# LoraWan_shield_v01.net
KiCad netlist of a schematic drawn in EAGLE
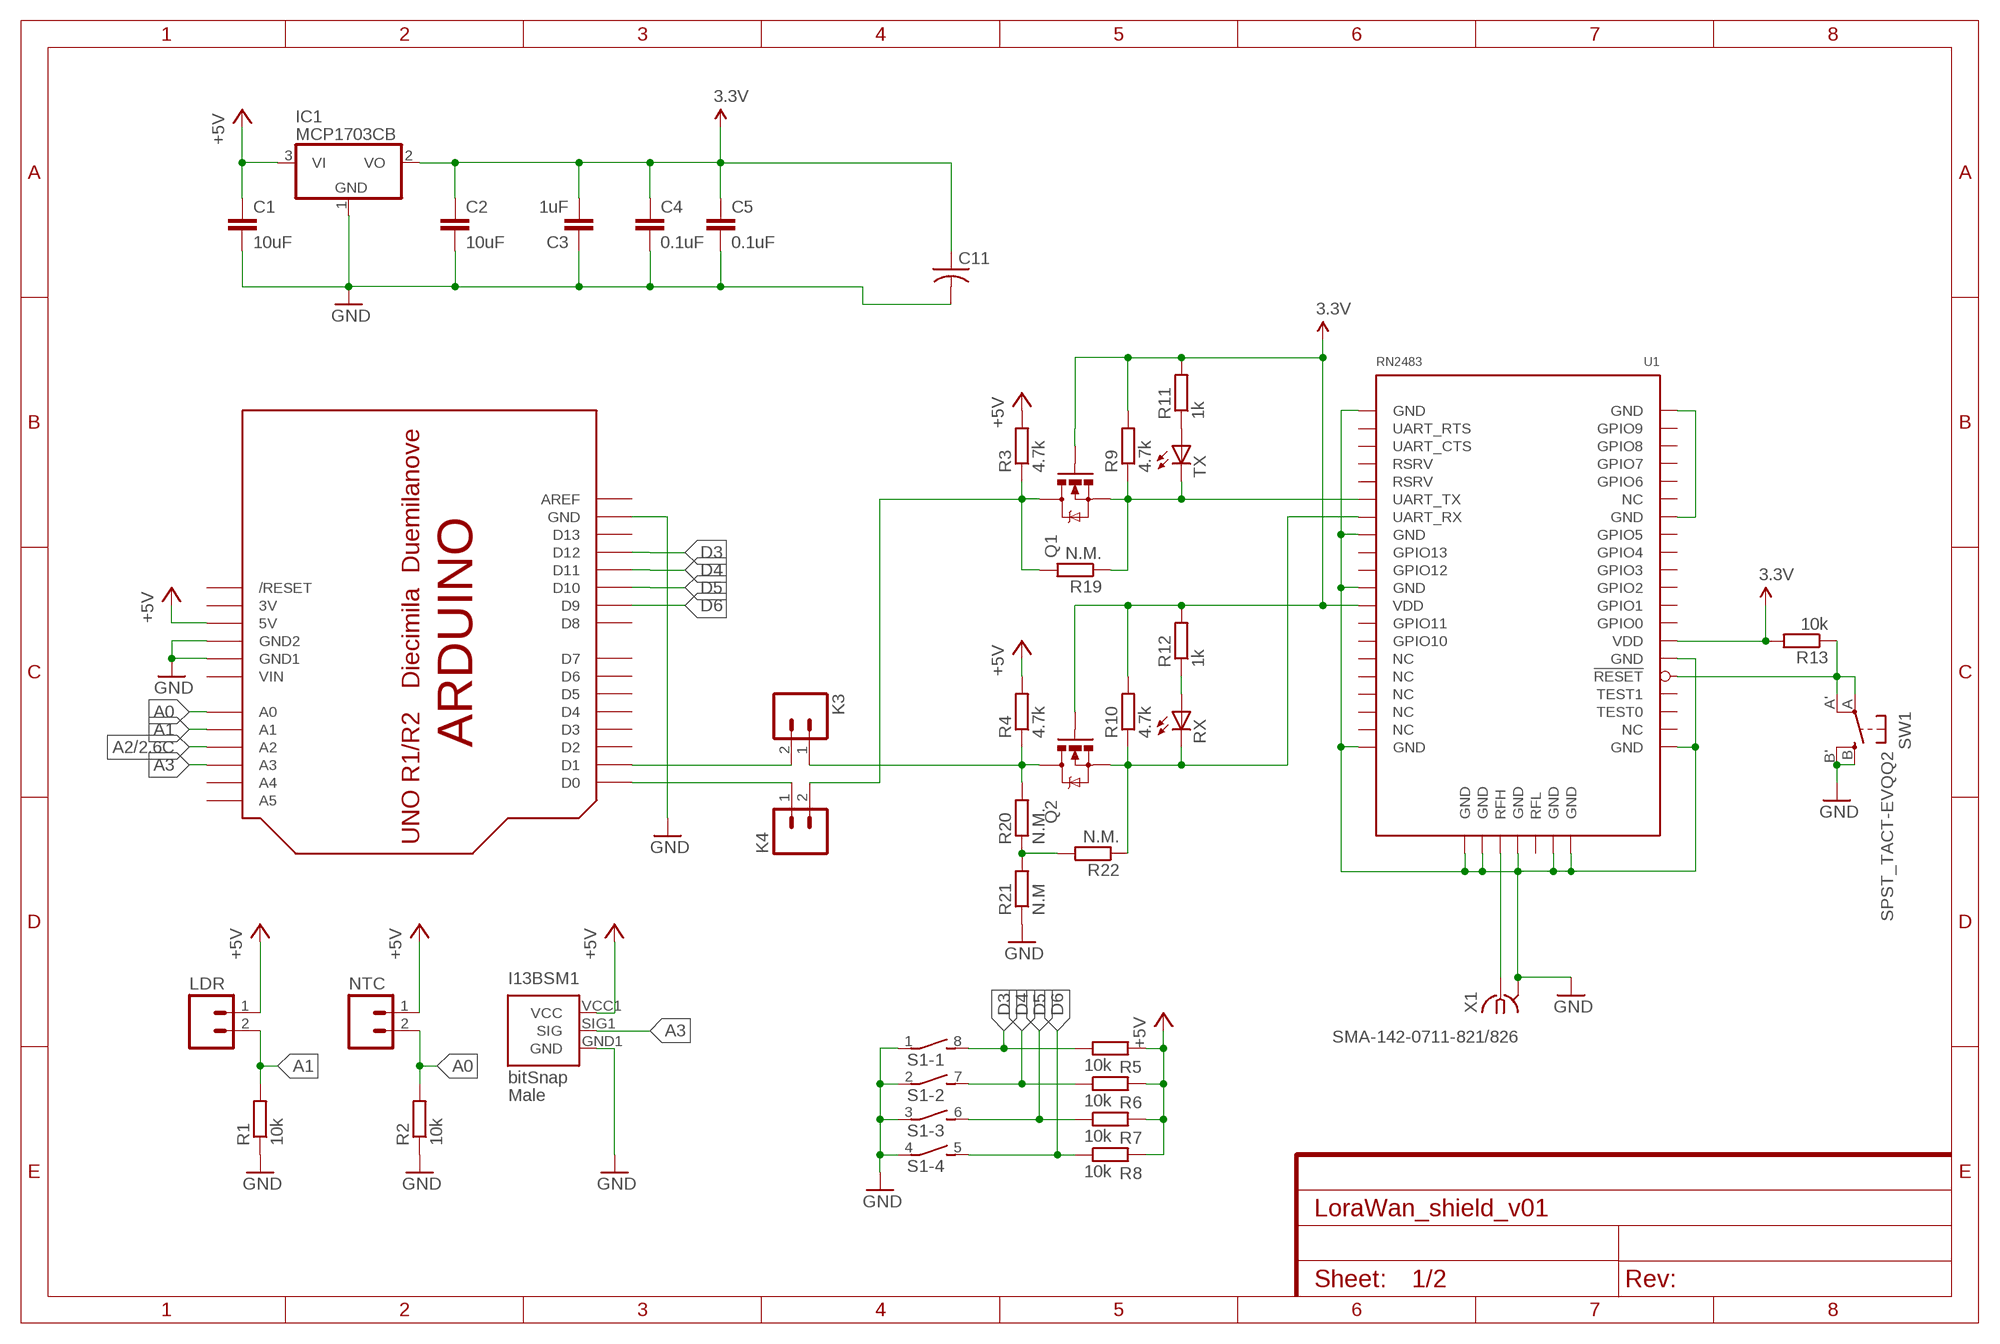
[diagram p0: schematic, sheet 1]
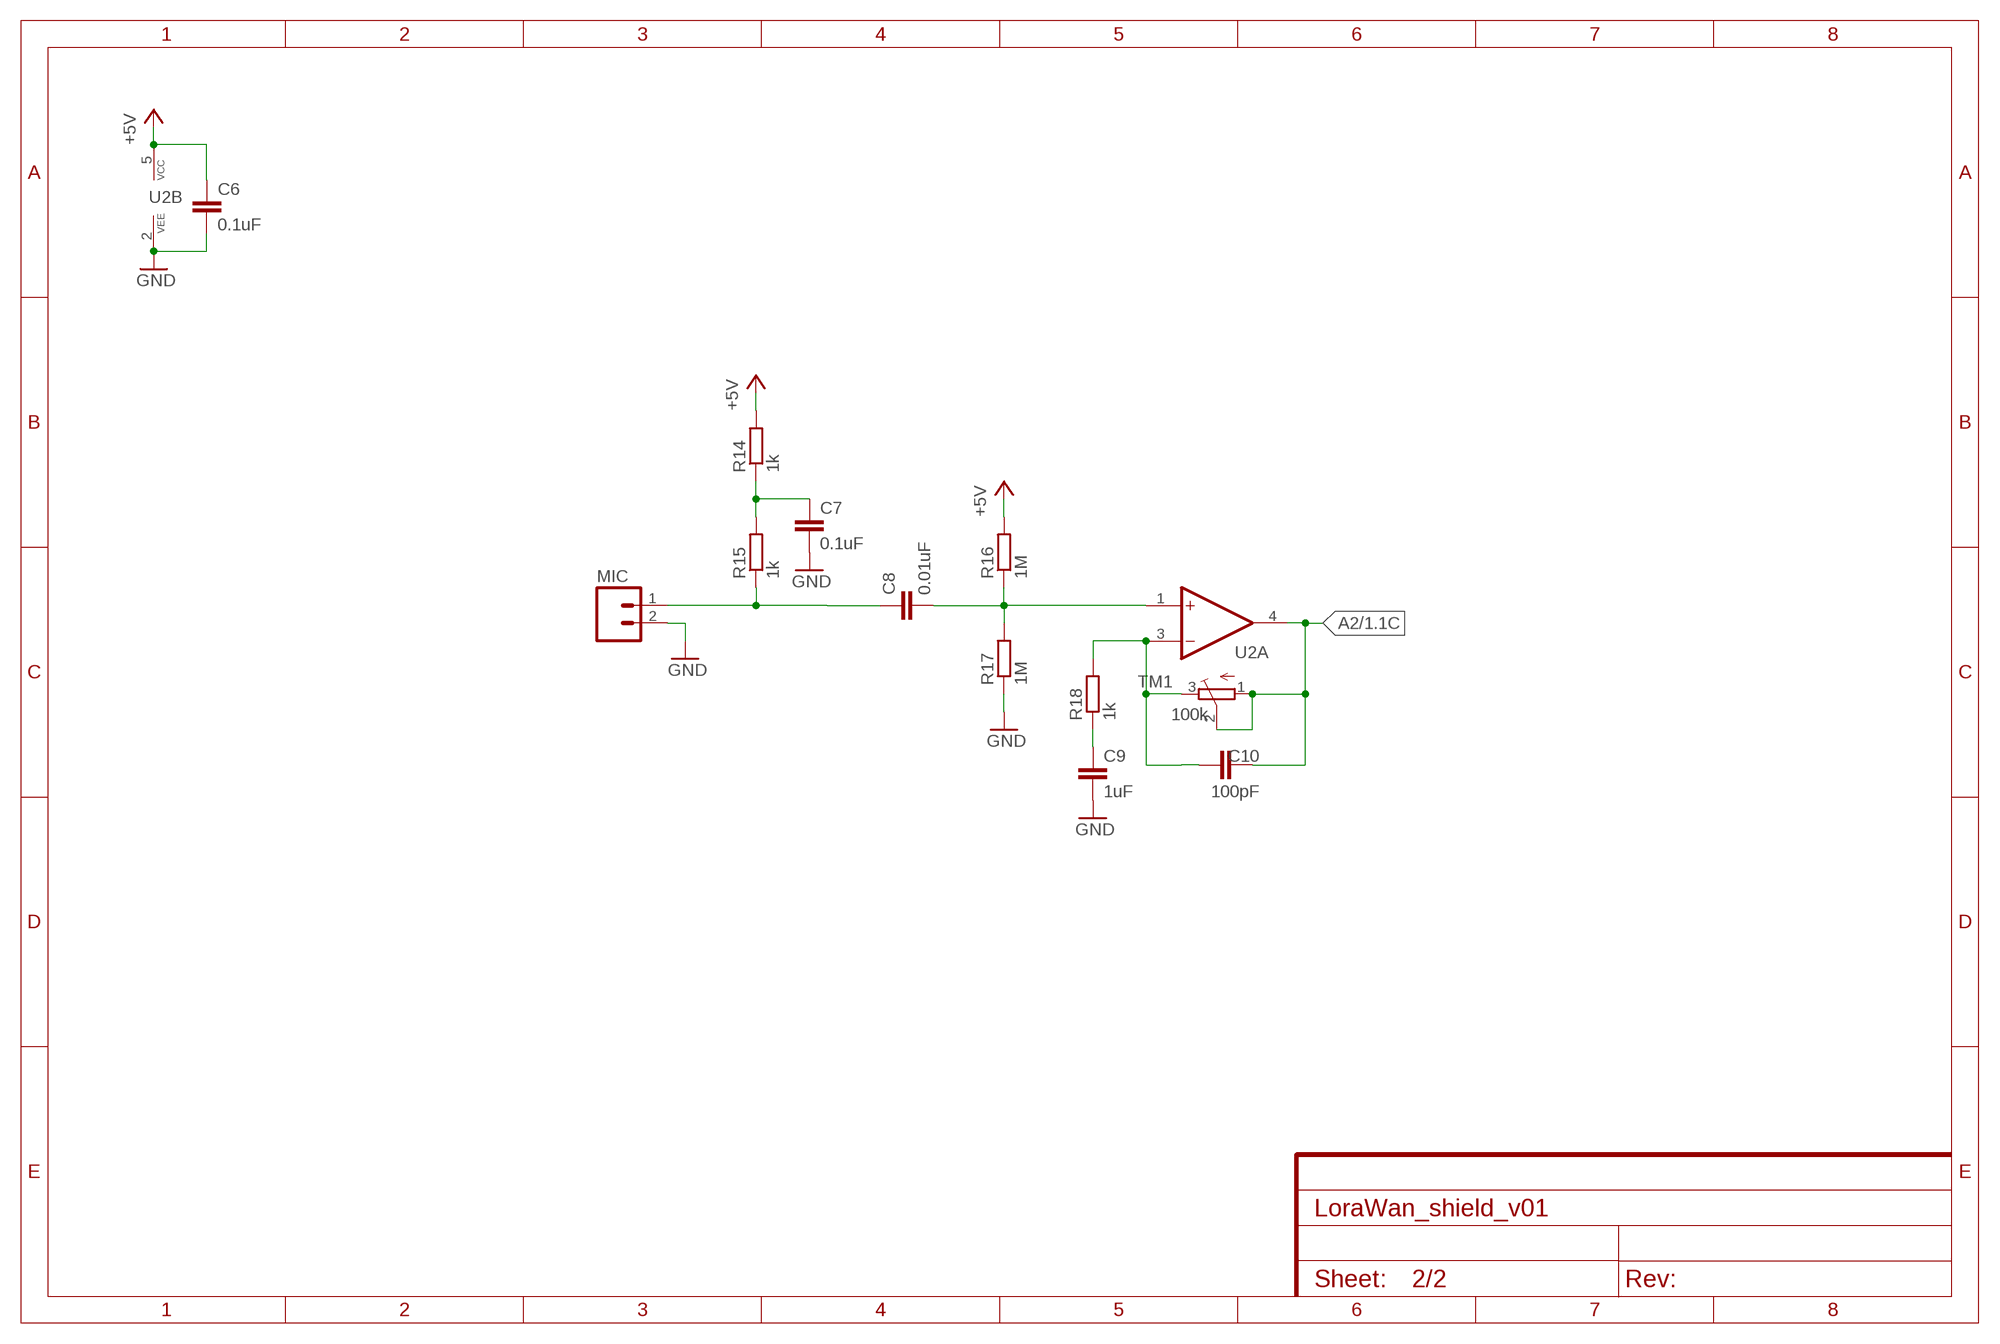
[diagram p1: schematic, sheet 2]

(export (version "E")
  (design (tool "Eeschema 10.0.6"))
  (components
    (comp (ref "C6")
      (value "0.1uF")
      (footprint "eagle-import:C0603K")
      (libsource (lib "eagle-import") (part "C-EUC0603K"))
    )
    (comp (ref "C7")
      (value "0.1uF")
      (footprint "eagle-import:C0603K")
      (libsource (lib "eagle-import") (part "C-EUC0603K"))
    )
    (comp (ref "C8")
      (value "0.01uF")
      (footprint "eagle-import:C0603K")
      (libsource (lib "eagle-import") (part "C-EUC0603K"))
    )
    (comp (ref "C9")
      (value "1uF")
      (footprint "eagle-import:C0603K")
      (libsource (lib "eagle-import") (part "C-EUC0603K"))
    )
    (comp (ref "C10")
      (value "100pF")
      (footprint "eagle-import:C0603K")
      (libsource (lib "eagle-import") (part "C-EUC0603K"))
    )
    (comp (ref "MIC")
      (value "M02LOCK_LONGPADS")
      (footprint "eagle-import:1X02_LOCK_LONGPADS")
      (libsource (lib "eagle-import") (part "M02LOCK_LONGPADS"))
    )
    (comp (ref "R14")
      (value "1k")
      (footprint "eagle-import:R0603")
      (libsource (lib "eagle-import") (part "R-EU_R0603"))
    )
    (comp (ref "R15")
      (value "1k")
      (footprint "eagle-import:R0603")
      (libsource (lib "eagle-import") (part "R-EU_R0603"))
    )
    (comp (ref "R16")
      (value "1M")
      (footprint "eagle-import:R0603")
      (libsource (lib "eagle-import") (part "R-EU_R0603"))
    )
    (comp (ref "R17")
      (value "1M")
      (footprint "eagle-import:R0603")
      (libsource (lib "eagle-import") (part "R-EU_R0603"))
    )
    (comp (ref "R18")
      (value "1k")
      (footprint "eagle-import:R0603")
      (libsource (lib "eagle-import") (part "R-EU_R0603"))
    )
    (comp (ref "TM1")
      (value "100k")
      (footprint "eagle-import:TC33X")
      (libsource (lib "eagle-import") (part "TRIMPOTTC33X"))
    )
    (comp (ref "U2")
      (value "MAX4466EXK+T")
      (footprint "eagle-import:SC70")
      (libsource (lib "eagle-import") (part "MAX4466EXK+T"))
    )
    (comp (ref "ARD1")
      (value "ARDUINO-NOHOLE")
      (footprint "eagle-import:ARDUINO-NOHOLE")
      (libsource (lib "eagle-import") (part "ARDUINO-NOHOLE"))
    )
    (comp (ref "C1")
      (value "10uF")
      (footprint "eagle-import:C0603K")
      (libsource (lib "eagle-import") (part "C-EUC0603K"))
    )
    (comp (ref "C2")
      (value "10uF")
      (footprint "eagle-import:C0603K")
      (libsource (lib "eagle-import") (part "C-EUC0603K"))
    )
    (comp (ref "C3")
      (value "1uF")
      (footprint "eagle-import:C0603K")
      (libsource (lib "eagle-import") (part "C-EUC0603K"))
    )
    (comp (ref "C4")
      (value "0.1uF")
      (footprint "eagle-import:C0603K")
      (libsource (lib "eagle-import") (part "C-EUC0603K"))
    )
    (comp (ref "C5")
      (value "0.1uF")
      (footprint "eagle-import:C0603K")
      (libsource (lib "eagle-import") (part "C-EUC0603K"))
    )
    (comp (ref "C11")
      (value "C-USC0603")
      (footprint "eagle-import:C0603")
      (libsource (lib "eagle-import") (part "C-USC0603"))
    )
    (comp (ref "I13BSM1")
      (value "BITSNAP_V03_MALE")
      (footprint "eagle-import:BITSNAP_V03_MALE")
      (libsource (lib "eagle-import") (part "BITSNAP_V03_MALE"))
    )
    (comp (ref "IC1")
      (value "MCP1703CB")
      (footprint "eagle-import:SOT23")
      (libsource (lib "eagle-import") (part "MCP1703CB"))
    )
    (comp (ref "K3")
      (value "M02LOCK_LONGPADS")
      (footprint "eagle-import:1X02_LOCK_LONGPADS")
      (libsource (lib "eagle-import") (part "M02LOCK_LONGPADS"))
    )
    (comp (ref "K4")
      (value "M02LOCK_LONGPADS")
      (footprint "eagle-import:1X02_LOCK_LONGPADS")
      (libsource (lib "eagle-import") (part "M02LOCK_LONGPADS"))
    )
    (comp (ref "LDR")
      (value "M02LOCK_LONGPADS")
      (footprint "eagle-import:1X02_LOCK_LONGPADS")
      (libsource (lib "eagle-import") (part "M02LOCK_LONGPADS"))
    )
    (comp (ref "NTC")
      (value "M02LOCK_LONGPADS")
      (footprint "eagle-import:1X02_LOCK_LONGPADS")
      (libsource (lib "eagle-import") (part "M02LOCK_LONGPADS"))
    )
    (comp (ref "Q1")
      (value "DMG1012T")
      (footprint "eagle-import:SOT523")
      (libsource (lib "eagle-import") (part "DMG1012T"))
    )
    (comp (ref "Q2")
      (value "DMG1012T")
      (footprint "eagle-import:SOT523")
      (libsource (lib "eagle-import") (part "DMG1012T"))
    )
    (comp (ref "R1")
      (value "10k")
      (footprint "eagle-import:R0603")
      (libsource (lib "eagle-import") (part "R-EU_R0603"))
    )
    (comp (ref "R2")
      (value "10k")
      (footprint "eagle-import:R0603")
      (libsource (lib "eagle-import") (part "R-EU_R0603"))
    )
    (comp (ref "R3")
      (value "4.7k")
      (footprint "eagle-import:R0603")
      (libsource (lib "eagle-import") (part "R-EU_R0603"))
    )
    (comp (ref "R4")
      (value "4.7k")
      (footprint "eagle-import:R0603")
      (libsource (lib "eagle-import") (part "R-EU_R0603"))
    )
    (comp (ref "R5")
      (value "10k")
      (footprint "eagle-import:R0603")
      (libsource (lib "eagle-import") (part "R-EU_R0603"))
    )
    (comp (ref "R6")
      (value "10k")
      (footprint "eagle-import:R0603")
      (libsource (lib "eagle-import") (part "R-EU_R0603"))
    )
    (comp (ref "R7")
      (value "10k")
      (footprint "eagle-import:R0603")
      (libsource (lib "eagle-import") (part "R-EU_R0603"))
    )
    (comp (ref "R8")
      (value "10k")
      (footprint "eagle-import:R0603")
      (libsource (lib "eagle-import") (part "R-EU_R0603"))
    )
    (comp (ref "R9")
      (value "4.7k")
      (footprint "eagle-import:R0603")
      (libsource (lib "eagle-import") (part "R-EU_R0603"))
    )
    (comp (ref "R10")
      (value "4.7k")
      (footprint "eagle-import:R0603")
      (libsource (lib "eagle-import") (part "R-EU_R0603"))
    )
    (comp (ref "R11")
      (value "1k")
      (footprint "eagle-import:R0603")
      (libsource (lib "eagle-import") (part "R-EU_R0603"))
    )
    (comp (ref "R12")
      (value "1k")
      (footprint "eagle-import:R0603")
      (libsource (lib "eagle-import") (part "R-EU_R0603"))
    )
    (comp (ref "R13")
      (value "10k")
      (footprint "eagle-import:R0603")
      (libsource (lib "eagle-import") (part "R-EU_R0603"))
    )
    (comp (ref "R19")
      (value "N.M.")
      (footprint "eagle-import:R0603")
      (libsource (lib "eagle-import") (part "R-EU_R0603"))
    )
    (comp (ref "R20")
      (value "N.M.")
      (footprint "eagle-import:R0603")
      (libsource (lib "eagle-import") (part "R-EU_R0603"))
    )
    (comp (ref "R21")
      (value "N.M")
      (footprint "eagle-import:R0603")
      (libsource (lib "eagle-import") (part "R-EU_R0603"))
    )
    (comp (ref "R22")
      (value "N.M.")
      (footprint "eagle-import:R0603")
      (libsource (lib "eagle-import") (part "R-EU_R0603"))
    )
    (comp (ref "RX")
      (value "LEDCHIPLED_0603")
      (footprint "eagle-import:CHIPLED_0603")
      (libsource (lib "eagle-import") (part "LEDCHIPLED_0603"))
    )
    (comp (ref "S1")
      (value "DIP04S")
      (footprint "eagle-import:DIP04S")
      (fields (field (name "OC_FARNELL") "9471570"))
      (libsource (lib "eagle-import") (part "DIP04S"))
    )
    (comp (ref "SW1")
      (value "SPST_TACT-EVQQ2")
      (footprint "eagle-import:EVQ-Q2")
      (libsource (lib "eagle-import") (part "SPST_TACT-EVQQ2"))
    )
    (comp (ref "TX")
      (value "LEDCHIPLED_0603")
      (footprint "eagle-import:CHIPLED_0603")
      (libsource (lib "eagle-import") (part "LEDCHIPLED_0603"))
    )
    (comp (ref "U1")
      (value "RN2483")
      (footprint "eagle-import:RN2483")
      (libsource (lib "eagle-import") (part "RN2483"))
    )
    (comp (ref "X1")
      (value "SMA-142-0711-821/826")
      (footprint "eagle-import:J502-ND-142-0711-821_826")
      (fields (field (name "MF") "JOHNSON COMPONENTS") (field (name "MPN") "142-0711-821"))
      (libsource (lib "eagle-import") (part "SMA-142-0711-821/826"))
    )
  )
  (nets
    (net (code "1") (name "+5V") (class "Default")
      (node (ref "ARD1") (pin "5V") (pinfunction "5V_5V") (pintype "power_in"))
      (node (ref "C1") (pin "1") (pinfunction "1_1") (pintype "passive"))
      (node (ref "C6") (pin "1") (pinfunction "1_1") (pintype "passive"))
      (node (ref "I13BSM1") (pin "VCC1") (pinfunction "VCC_VCC1") (pintype "bidirectional"))
      (node (ref "IC1") (pin "3") (pinfunction "VI_3") (pintype "input"))
      (node (ref "LDR") (pin "1") (pinfunction "1_1") (pintype "passive"))
      (node (ref "NTC") (pin "1") (pinfunction "1_1") (pintype "passive"))
      (node (ref "R14") (pin "2") (pinfunction "2_2") (pintype "passive"))
      (node (ref "R16") (pin "2") (pinfunction "2_2") (pintype "passive"))
      (node (ref "R3") (pin "2") (pinfunction "2_2") (pintype "passive"))
      (node (ref "R4") (pin "2") (pinfunction "2_2") (pintype "passive"))
      (node (ref "R5") (pin "2") (pinfunction "2_2") (pintype "passive"))
      (node (ref "R6") (pin "2") (pinfunction "2_2") (pintype "passive"))
      (node (ref "R7") (pin "2") (pinfunction "2_2") (pintype "passive"))
      (node (ref "R8") (pin "2") (pinfunction "2_2") (pintype "passive"))
      (node (ref "U2") (pin "5") (pinfunction "VCC_5") (pintype "power_in"))
    )
    (net (code "2") (name "3.3V") (class "Default")
      (node (ref "C11") (pin "1") (pinfunction "1_1") (pintype "passive"))
      (node (ref "C2") (pin "1") (pinfunction "1_1") (pintype "passive"))
      (node (ref "C3") (pin "2") (pinfunction "2_2") (pintype "passive"))
      (node (ref "C4") (pin "1") (pinfunction "1_1") (pintype "passive"))
      (node (ref "C5") (pin "1") (pinfunction "1_1") (pintype "passive"))
      (node (ref "IC1") (pin "2") (pinfunction "VO_2") (pintype "passive"))
      (node (ref "Q1") (pin "1") (pinfunction "G_1") (pintype "passive"))
      (node (ref "Q2") (pin "1") (pinfunction "G_1") (pintype "passive"))
      (node (ref "R10") (pin "2") (pinfunction "2_2") (pintype "passive"))
      (node (ref "R11") (pin "2") (pinfunction "2_2") (pintype "passive"))
      (node (ref "R12") (pin "2") (pinfunction "2_2") (pintype "passive"))
      (node (ref "R13") (pin "2") (pinfunction "2_2") (pintype "passive"))
      (node (ref "R9") (pin "2") (pinfunction "2_2") (pintype "passive"))
      (node (ref "U1") (pin "12") (pinfunction "VDD_12") (pintype "power_in"))
      (node (ref "U1") (pin "34") (pinfunction "VDD_34") (pintype "power_in"))
    )
    (net (code "3") (name "3V") (class "Default")
      (node (ref "ARD1") (pin "3V") (pinfunction "3V_3V") (pintype "power_in"))
    )
    (net (code "4") (name "A0") (class "Default")
      (node (ref "ARD1") (pin "A0") (pinfunction "A0_A0") (pintype "bidirectional"))
      (node (ref "NTC") (pin "2") (pinfunction "2_2") (pintype "passive"))
      (node (ref "R2") (pin "2") (pinfunction "2_2") (pintype "passive"))
    )
    (net (code "5") (name "A1") (class "Default")
      (node (ref "ARD1") (pin "A1") (pinfunction "A1_A1") (pintype "bidirectional"))
      (node (ref "LDR") (pin "2") (pinfunction "2_2") (pintype "passive"))
      (node (ref "R1") (pin "2") (pinfunction "2_2") (pintype "passive"))
    )
    (net (code "6") (name "A2") (class "Default")
      (node (ref "ARD1") (pin "A2") (pinfunction "A2_A2") (pintype "bidirectional"))
      (node (ref "C10") (pin "2") (pinfunction "2_2") (pintype "passive"))
      (node (ref "TM1") (pin "1") (pinfunction "A_1") (pintype "passive"))
      (node (ref "TM1") (pin "2") (pinfunction "S_2") (pintype "passive"))
      (node (ref "U2") (pin "4") (pinfunction "OUT_4") (pintype "output"))
    )
    (net (code "7") (name "A3") (class "Default")
      (node (ref "ARD1") (pin "A3") (pinfunction "A3_A3") (pintype "bidirectional"))
      (node (ref "I13BSM1") (pin "SIG1") (pinfunction "SIG_SIG1") (pintype "bidirectional"))
    )
    (net (code "8") (name "D3") (class "Default")
      (node (ref "ARD1") (pin "D12") (pinfunction "D12_D12") (pintype "bidirectional"))
      (node (ref "R5") (pin "1") (pinfunction "1_1") (pintype "passive"))
      (node (ref "S1") (pin "8") (pinfunction "2_8") (pintype "passive"))
    )
    (net (code "9") (name "D4") (class "Default")
      (node (ref "ARD1") (pin "D11") (pinfunction "D11_D11") (pintype "bidirectional"))
      (node (ref "R6") (pin "1") (pinfunction "1_1") (pintype "passive"))
      (node (ref "S1") (pin "7") (pinfunction "2_7") (pintype "passive"))
    )
    (net (code "10") (name "D5") (class "Default")
      (node (ref "ARD1") (pin "D10") (pinfunction "D10_D10") (pintype "bidirectional"))
      (node (ref "R7") (pin "1") (pinfunction "1_1") (pintype "passive"))
      (node (ref "S1") (pin "6") (pinfunction "2_6") (pintype "passive"))
    )
    (net (code "11") (name "D6") (class "Default")
      (node (ref "ARD1") (pin "D9") (pinfunction "D9_D9") (pintype "bidirectional"))
      (node (ref "R8") (pin "1") (pinfunction "1_1") (pintype "passive"))
      (node (ref "S1") (pin "5") (pinfunction "2_5") (pintype "passive"))
    )
    (net (code "12") (name "GND") (class "Default")
      (node (ref "ARD1") (pin "GND") (pinfunction "GND_GND") (pintype "power_in"))
      (node (ref "ARD1") (pin "GND1") (pinfunction "GND1_GND1") (pintype "power_in"))
      (node (ref "ARD1") (pin "GND2") (pinfunction "GND2_GND2") (pintype "power_in"))
      (node (ref "C1") (pin "2") (pinfunction "2_2") (pintype "passive"))
      (node (ref "C11") (pin "2") (pinfunction "2_2") (pintype "passive"))
      (node (ref "C2") (pin "2") (pinfunction "2_2") (pintype "passive"))
      (node (ref "C3") (pin "1") (pinfunction "1_1") (pintype "passive"))
      (node (ref "C4") (pin "2") (pinfunction "2_2") (pintype "passive"))
      (node (ref "C5") (pin "2") (pinfunction "2_2") (pintype "passive"))
      (node (ref "C6") (pin "2") (pinfunction "2_2") (pintype "passive"))
      (node (ref "C7") (pin "2") (pinfunction "2_2") (pintype "passive"))
      (node (ref "C9") (pin "2") (pinfunction "2_2") (pintype "passive"))
      (node (ref "I13BSM1") (pin "GND1") (pinfunction "GND_GND1") (pintype "bidirectional"))
      (node (ref "IC1") (pin "1") (pinfunction "GND_1") (pintype "passive"))
      (node (ref "MIC") (pin "2") (pinfunction "2_2") (pintype "passive"))
      (node (ref "R1") (pin "1") (pinfunction "1_1") (pintype "passive"))
      (node (ref "R17") (pin "1") (pinfunction "1_1") (pintype "passive"))
      (node (ref "R2") (pin "1") (pinfunction "1_1") (pintype "passive"))
      (node (ref "R21") (pin "1") (pinfunction "1_1") (pintype "passive"))
      (node (ref "S1") (pin "1") (pinfunction "1_1") (pintype "passive"))
      (node (ref "S1") (pin "2") (pinfunction "1_2") (pintype "passive"))
      (node (ref "S1") (pin "3") (pinfunction "1_3") (pintype "passive"))
      (node (ref "S1") (pin "4") (pinfunction "1_4") (pintype "passive"))
      (node (ref "SW1") (pin "B") (pinfunction "S_B") (pintype "passive"))
      (node (ref "SW1") (pin "B'") (pinfunction "S1_B'") (pintype "passive"))
      (node (ref "U1") (pin "1") (pinfunction "GND_1") (pintype "power_in"))
      (node (ref "U1") (pin "11") (pinfunction "GND_11") (pintype "power_in"))
      (node (ref "U1") (pin "20") (pinfunction "GND_20") (pintype "power_in"))
      (node (ref "U1") (pin "21") (pinfunction "GND_21") (pintype "power_in"))
      (node (ref "U1") (pin "22") (pinfunction "GND_22") (pintype "power_in"))
      (node (ref "U1") (pin "24") (pinfunction "GND_24") (pintype "power_in"))
      (node (ref "U1") (pin "26") (pinfunction "GND_26") (pintype "power_in"))
      (node (ref "U1") (pin "27") (pinfunction "GND_27") (pintype "power_in"))
      (node (ref "U1") (pin "28") (pinfunction "GND_28") (pintype "power_in"))
      (node (ref "U1") (pin "33") (pinfunction "GND_33") (pintype "power_in"))
      (node (ref "U1") (pin "8") (pinfunction "GND_8") (pintype "power_in"))
      (node (ref "U2") (pin "2") (pinfunction "VEE_2") (pintype "power_in"))
      (node (ref "X1") (pin "G@1") (pinfunction "2_G@1") (pintype "passive"))
      (node (ref "X1") (pin "G@2") (pinfunction "2_G@2") (pintype "passive"))
      (node (ref "X1") (pin "G@3") (pinfunction "2_G@3") (pintype "passive"))
      (node (ref "X1") (pin "G@4") (pinfunction "2_G@4") (pintype "passive"))
    )
    (net (code "13") (name "Net-(ARD1-PadD0)") (class "Default")
      (node (ref "ARD1") (pin "D0") (pinfunction "D0_D0") (pintype "bidirectional"))
      (node (ref "K4") (pin "1") (pinfunction "1_1") (pintype "passive"))
    )
    (net (code "14") (name "Net-(ARD1-PadD1)") (class "Default")
      (node (ref "ARD1") (pin "D1") (pinfunction "D1_D1") (pintype "bidirectional"))
      (node (ref "K3") (pin "2") (pinfunction "2_2") (pintype "passive"))
    )
    (net (code "15") (name "Net-(C7-Pad1)") (class "Default")
      (node (ref "C7") (pin "1") (pinfunction "1_1") (pintype "passive"))
      (node (ref "R14") (pin "1") (pinfunction "1_1") (pintype "passive"))
      (node (ref "R15") (pin "2") (pinfunction "2_2") (pintype "passive"))
    )
    (net (code "16") (name "Net-(C8-Pad1)") (class "Default")
      (node (ref "C8") (pin "1") (pinfunction "1_1") (pintype "passive"))
      (node (ref "MIC") (pin "1") (pinfunction "1_1") (pintype "passive"))
      (node (ref "R15") (pin "1") (pinfunction "1_1") (pintype "passive"))
    )
    (net (code "17") (name "Net-(C9-Pad1)") (class "Default")
      (node (ref "C9") (pin "1") (pinfunction "1_1") (pintype "passive"))
      (node (ref "R18") (pin "1") (pinfunction "1_1") (pintype "passive"))
    )
    (net (code "18") (name "Net-(Q1-D)") (class "Default")
      (node (ref "K4") (pin "2") (pinfunction "2_2") (pintype "passive"))
      (node (ref "Q1") (pin "3") (pinfunction "D_3") (pintype "passive"))
      (node (ref "R19") (pin "2") (pinfunction "2_2") (pintype "passive"))
      (node (ref "R3") (pin "1") (pinfunction "1_1") (pintype "passive"))
    )
    (net (code "19") (name "Net-(Q1-S)") (class "Default")
      (node (ref "Q1") (pin "2") (pinfunction "S_2") (pintype "passive"))
      (node (ref "R19") (pin "1") (pinfunction "1_1") (pintype "passive"))
      (node (ref "R9") (pin "1") (pinfunction "1_1") (pintype "passive"))
      (node (ref "TX") (pin "C") (pinfunction "C_C") (pintype "passive"))
      (node (ref "U1") (pin "6") (pinfunction "UART_TX_6") (pintype "output"))
    )
    (net (code "20") (name "Net-(Q2-D)") (class "Default")
      (node (ref "K3") (pin "1") (pinfunction "1_1") (pintype "passive"))
      (node (ref "Q2") (pin "3") (pinfunction "D_3") (pintype "passive"))
      (node (ref "R20") (pin "2") (pinfunction "2_2") (pintype "passive"))
      (node (ref "R4") (pin "1") (pinfunction "1_1") (pintype "passive"))
    )
    (net (code "21") (name "Net-(Q2-S)") (class "Default")
      (node (ref "Q2") (pin "2") (pinfunction "S_2") (pintype "passive"))
      (node (ref "R10") (pin "1") (pinfunction "1_1") (pintype "passive"))
      (node (ref "R22") (pin "1") (pinfunction "1_1") (pintype "passive"))
      (node (ref "RX") (pin "C") (pinfunction "C_C") (pintype "passive"))
      (node (ref "U1") (pin "7") (pinfunction "UART_RX_7") (pintype "input"))
    )
    (net (code "22") (name "Net-(R11-Pad1)") (class "Default")
      (node (ref "R11") (pin "1") (pinfunction "1_1") (pintype "passive"))
      (node (ref "TX") (pin "A") (pinfunction "A_A") (pintype "passive"))
    )
    (net (code "23") (name "Net-(R12-Pad1)") (class "Default")
      (node (ref "R12") (pin "1") (pinfunction "1_1") (pintype "passive"))
      (node (ref "RX") (pin "A") (pinfunction "A_A") (pintype "passive"))
    )
    (net (code "24") (name "Net-(R20-Pad1)") (class "Default")
      (node (ref "R20") (pin "1") (pinfunction "1_1") (pintype "passive"))
      (node (ref "R21") (pin "2") (pinfunction "2_2") (pintype "passive"))
      (node (ref "R22") (pin "2") (pinfunction "2_2") (pintype "passive"))
    )
    (net (code "25") (name "Net-(SW1-P)") (class "Default")
      (node (ref "R13") (pin "1") (pinfunction "1_1") (pintype "passive"))
      (node (ref "SW1") (pin "A") (pinfunction "P_A") (pintype "passive"))
      (node (ref "SW1") (pin "A'") (pinfunction "P1_A'") (pintype "passive"))
      (node (ref "U1") (pin "32") (pinfunction "~{RESET}_32") (pintype "input"))
    )
    (net (code "26") (name "Net-(TM1-E)") (class "Default")
      (node (ref "C10") (pin "1") (pinfunction "1_1") (pintype "passive"))
      (node (ref "R18") (pin "2") (pinfunction "2_2") (pintype "passive"))
      (node (ref "TM1") (pin "3") (pinfunction "E_3") (pintype "passive"))
      (node (ref "U2") (pin "3") (pinfunction "-IN_3") (pintype "input"))
    )
    (net (code "27") (name "Net-(U1-GND-Pad41)") (class "Default")
      (node (ref "U1") (pin "41") (pinfunction "GND_41") (pintype "power_in"))
      (node (ref "U1") (pin "47") (pinfunction "GND_47") (pintype "power_in"))
    )
    (net (code "28") (name "Net-(U1-RFH)") (class "Default")
      (node (ref "U1") (pin "23") (pinfunction "RFH_23") (pintype "bidirectional"))
      (node (ref "X1") (pin "1") (pinfunction "1_1") (pintype "passive"))
    )
    (net (code "29") (name "Net-(U2A-+IN)") (class "Default")
      (node (ref "C8") (pin "2") (pinfunction "2_2") (pintype "passive"))
      (node (ref "R16") (pin "1") (pinfunction "1_1") (pintype "passive"))
      (node (ref "R17") (pin "2") (pinfunction "2_2") (pintype "passive"))
      (node (ref "U2") (pin "1") (pinfunction "+IN_1") (pintype "input"))
    )
    (net (code "30") (name "VIN") (class "Default")
      (node (ref "ARD1") (pin "VIN") (pinfunction "VIN_VIN") (pintype "power_in"))
    )
    (net (code "31") (name "unconnected-(ARD1-PadA4)") (class "Default")
      (node (ref "ARD1") (pin "A4") (pinfunction "A4_A4") (pintype "bidirectional"))
    )
    (net (code "32") (name "unconnected-(ARD1-PadA5)") (class "Default")
      (node (ref "ARD1") (pin "A5") (pinfunction "A5_A5") (pintype "bidirectional"))
    )
    (net (code "33") (name "unconnected-(ARD1-PadAREF)") (class "Default")
      (node (ref "ARD1") (pin "AREF") (pinfunction "AREF_AREF") (pintype "bidirectional"))
    )
    (net (code "34") (name "unconnected-(ARD1-PadD2)") (class "Default")
      (node (ref "ARD1") (pin "D2") (pinfunction "D2_D2") (pintype "bidirectional"))
    )
    (net (code "35") (name "unconnected-(ARD1-PadD3)") (class "Default")
      (node (ref "ARD1") (pin "D3") (pinfunction "D3_D3") (pintype "bidirectional"))
    )
    (net (code "36") (name "unconnected-(ARD1-PadD4)") (class "Default")
      (node (ref "ARD1") (pin "D4") (pinfunction "D4_D4") (pintype "bidirectional"))
    )
    (net (code "37") (name "unconnected-(ARD1-PadD5)") (class "Default")
      (node (ref "ARD1") (pin "D5") (pinfunction "D5_D5") (pintype "bidirectional"))
    )
    (net (code "38") (name "unconnected-(ARD1-PadD6)") (class "Default")
      (node (ref "ARD1") (pin "D6") (pinfunction "D6_D6") (pintype "bidirectional"))
    )
    (net (code "39") (name "unconnected-(ARD1-PadD7)") (class "Default")
      (node (ref "ARD1") (pin "D7") (pinfunction "D7_D7") (pintype "bidirectional"))
    )
    (net (code "40") (name "unconnected-(ARD1-PadD8)") (class "Default")
      (node (ref "ARD1") (pin "D8") (pinfunction "D8_D8") (pintype "bidirectional"))
    )
    (net (code "41") (name "unconnected-(ARD1-PadD13)") (class "Default")
      (node (ref "ARD1") (pin "D13") (pinfunction "D13_D13") (pintype "bidirectional"))
    )
    (net (code "42") (name "unconnected-(ARD1-{slash}RESET-PadRESET)") (class "Default")
      (node (ref "ARD1") (pin "RESET") (pinfunction "/RESET_RESET") (pintype "bidirectional"))
    )
    (net (code "43") (name "unconnected-(U1-GPIO0-Pad35)") (class "Default")
      (node (ref "U1") (pin "35") (pinfunction "GPIO0_35") (pintype "bidirectional"))
    )
    (net (code "44") (name "unconnected-(U1-GPIO1-Pad36)") (class "Default")
      (node (ref "U1") (pin "36") (pinfunction "GPIO1_36") (pintype "bidirectional"))
    )
    (net (code "45") (name "unconnected-(U1-GPIO2-Pad37)") (class "Default")
      (node (ref "U1") (pin "37") (pinfunction "GPIO2_37") (pintype "bidirectional"))
    )
    (net (code "46") (name "unconnected-(U1-GPIO3-Pad38)") (class "Default")
      (node (ref "U1") (pin "38") (pinfunction "GPIO3_38") (pintype "bidirectional"))
    )
    (net (code "47") (name "unconnected-(U1-GPIO4-Pad39)") (class "Default")
      (node (ref "U1") (pin "39") (pinfunction "GPIO4_39") (pintype "bidirectional"))
    )
    (net (code "48") (name "unconnected-(U1-GPIO5-Pad40)") (class "Default")
      (node (ref "U1") (pin "40") (pinfunction "GPIO5_40") (pintype "bidirectional"))
    )
    (net (code "49") (name "unconnected-(U1-GPIO6-Pad43)") (class "Default")
      (node (ref "U1") (pin "43") (pinfunction "GPIO6_43") (pintype "bidirectional"))
    )
    (net (code "50") (name "unconnected-(U1-GPIO7-Pad44)") (class "Default")
      (node (ref "U1") (pin "44") (pinfunction "GPIO7_44") (pintype "bidirectional"))
    )
    (net (code "51") (name "unconnected-(U1-GPIO8-Pad45)") (class "Default")
      (node (ref "U1") (pin "45") (pinfunction "GPIO8_45") (pintype "bidirectional"))
    )
    (net (code "52") (name "unconnected-(U1-GPIO9-Pad46)") (class "Default")
      (node (ref "U1") (pin "46") (pinfunction "GPIO9_46") (pintype "bidirectional"))
    )
    (net (code "53") (name "unconnected-(U1-GPIO10-Pad14)") (class "Default")
      (node (ref "U1") (pin "14") (pinfunction "GPIO10_14") (pintype "bidirectional"))
    )
    (net (code "54") (name "unconnected-(U1-GPIO11-Pad13)") (class "Default")
      (node (ref "U1") (pin "13") (pinfunction "GPIO11_13") (pintype "bidirectional"))
    )
    (net (code "55") (name "unconnected-(U1-GPIO12-Pad10)") (class "Default")
      (node (ref "U1") (pin "10") (pinfunction "GPIO12_10") (pintype "bidirectional"))
    )
    (net (code "56") (name "unconnected-(U1-GPIO13-Pad9)") (class "Default")
      (node (ref "U1") (pin "9") (pinfunction "GPIO13_9") (pintype "bidirectional"))
    )
    (net (code "57") (name "unconnected-(U1-NC-Pad15)") (class "Default")
      (node (ref "U1") (pin "15") (pinfunction "NC_15") (pintype "no_connect"))
    )
    (net (code "58") (name "unconnected-(U1-NC-Pad16)") (class "Default")
      (node (ref "U1") (pin "16") (pinfunction "NC_16") (pintype "no_connect"))
    )
    (net (code "59") (name "unconnected-(U1-NC-Pad17)") (class "Default")
      (node (ref "U1") (pin "17") (pinfunction "NC_17") (pintype "no_connect"))
    )
    (net (code "60") (name "unconnected-(U1-NC-Pad18)") (class "Default")
      (node (ref "U1") (pin "18") (pinfunction "NC_18") (pintype "no_connect"))
    )
    (net (code "61") (name "unconnected-(U1-NC-Pad19)") (class "Default")
      (node (ref "U1") (pin "19") (pinfunction "NC_19") (pintype "no_connect"))
    )
    (net (code "62") (name "unconnected-(U1-NC-Pad29)") (class "Default")
      (node (ref "U1") (pin "29") (pinfunction "NC_29") (pintype "no_connect"))
    )
    (net (code "63") (name "unconnected-(U1-NC-Pad42)") (class "Default")
      (node (ref "U1") (pin "42") (pinfunction "NC_42") (pintype "no_connect"))
    )
    (net (code "64") (name "unconnected-(U1-RFL-Pad25)") (class "Default")
      (node (ref "U1") (pin "25") (pinfunction "RFL_25") (pintype "bidirectional"))
    )
    (net (code "65") (name "unconnected-(U1-RSRV-Pad4)") (class "Default")
      (node (ref "U1") (pin "4") (pinfunction "RSRV_4") (pintype "no_connect"))
    )
    (net (code "66") (name "unconnected-(U1-RSRV-Pad5)") (class "Default")
      (node (ref "U1") (pin "5") (pinfunction "RSRV_5") (pintype "no_connect"))
    )
    (net (code "67") (name "unconnected-(U1-TEST0-Pad30)") (class "Default")
      (node (ref "U1") (pin "30") (pinfunction "TEST0_30") (pintype "bidirectional"))
    )
    (net (code "68") (name "unconnected-(U1-TEST1-Pad31)") (class "Default")
      (node (ref "U1") (pin "31") (pinfunction "TEST1_31") (pintype "bidirectional"))
    )
    (net (code "69") (name "unconnected-(U1-UART_CTS-Pad3)") (class "Default")
      (node (ref "U1") (pin "3") (pinfunction "UART_CTS_3") (pintype "output"))
    )
    (net (code "70") (name "unconnected-(U1-UART_RTS-Pad2)") (class "Default")
      (node (ref "U1") (pin "2") (pinfunction "UART_RTS_2") (pintype "bidirectional"))
    )
  )
)
